# tiny-avionics.net
KiCad netlist of a schematic drawn in EAGLE
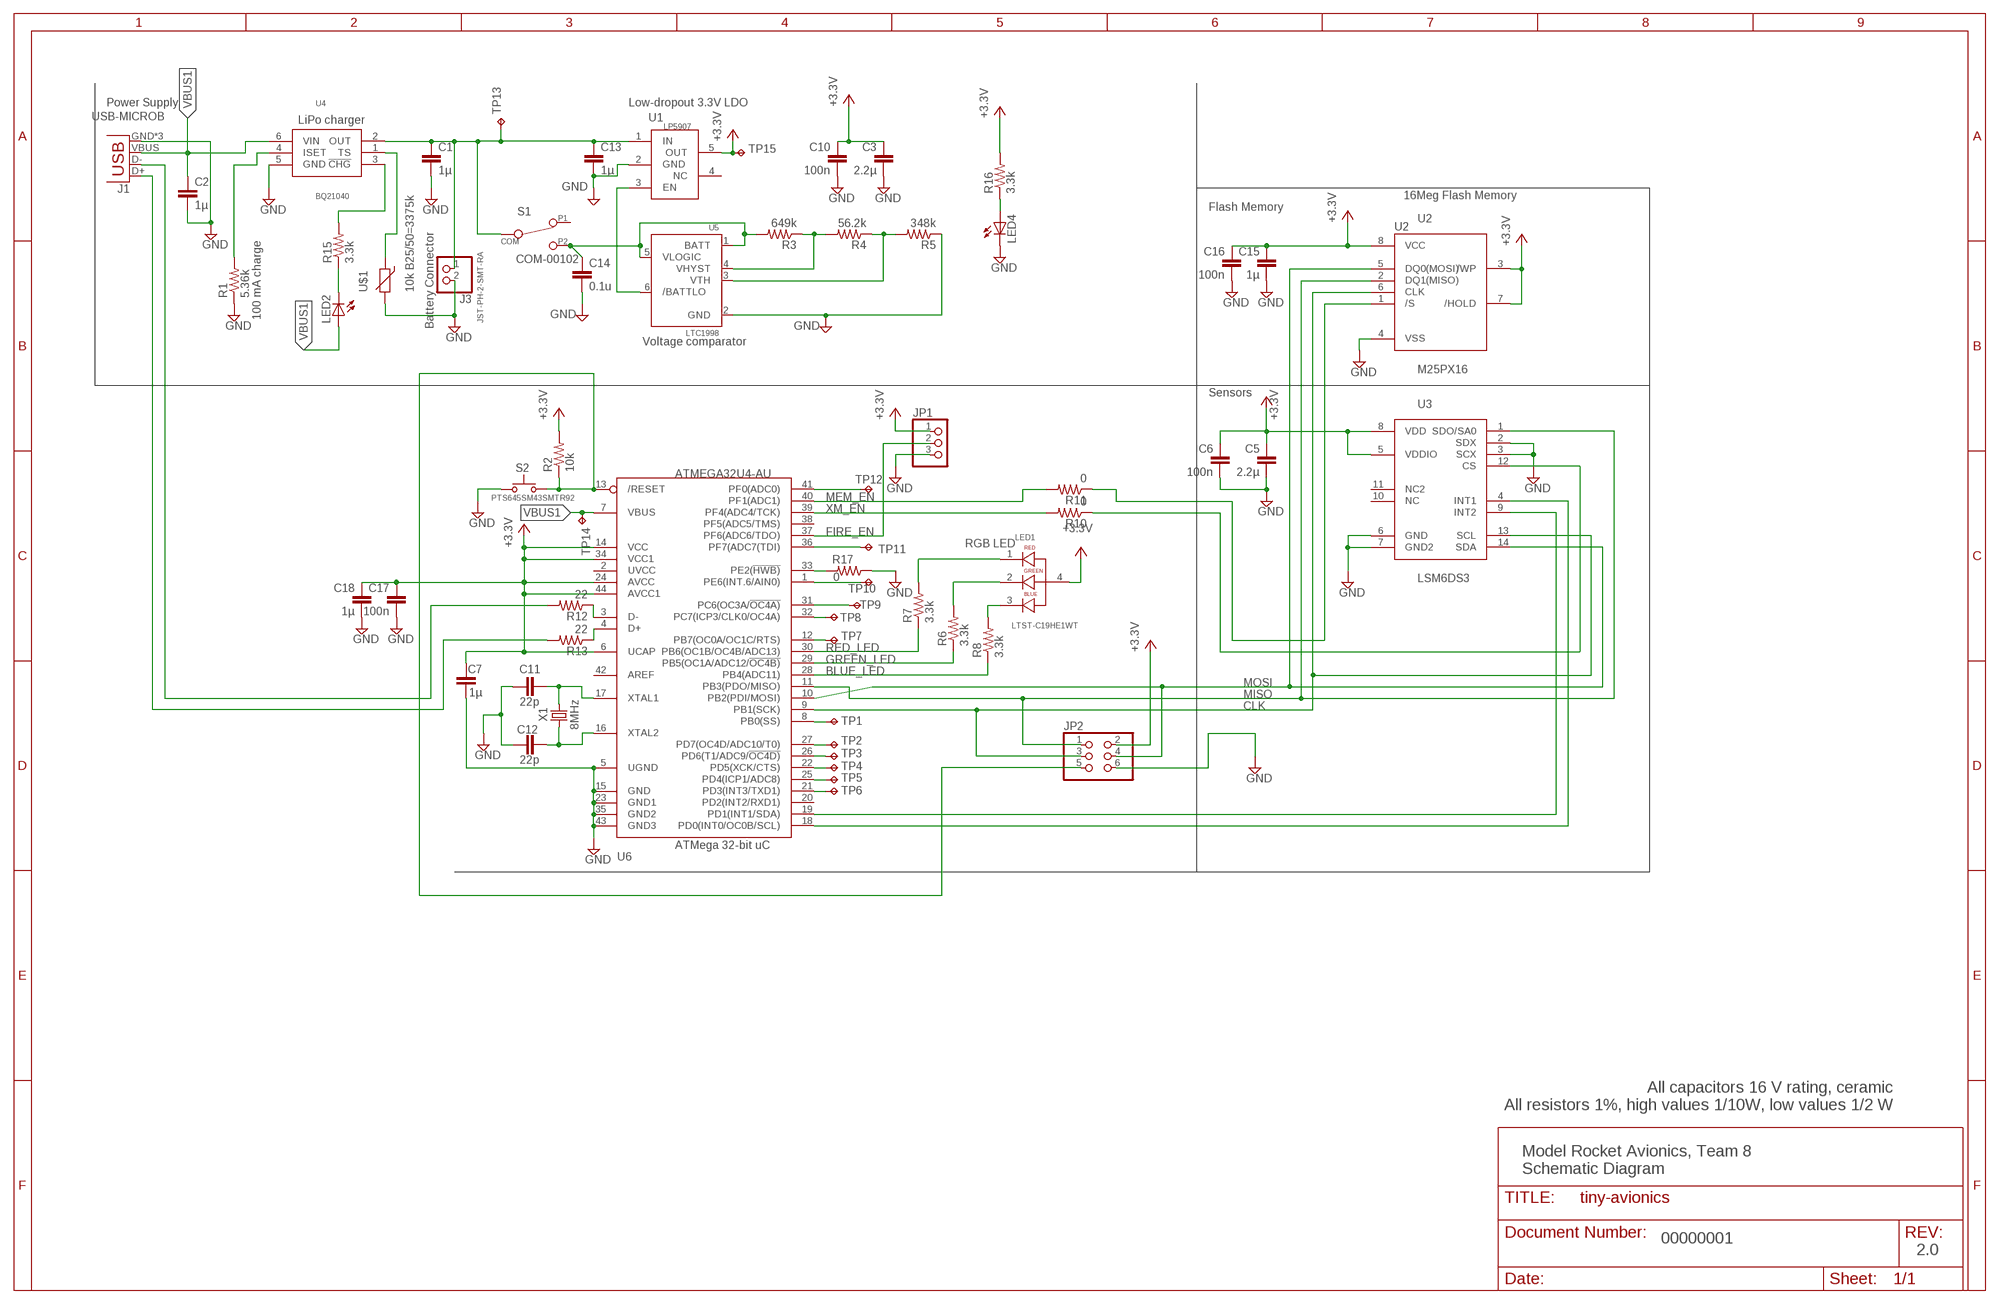
[diagram p0: schematic, sheet 1]

(export (version "E")
  (design (tool "Eeschema 10.0.6"))
  (components
    (comp (ref "C1")
      (value "1µ")
      (footprint "eagle-import:C0603")
      (libsource (lib "eagle-import") (part "C-EUC0603"))
    )
    (comp (ref "C2")
      (value "1µ")
      (footprint "eagle-import:C0603")
      (libsource (lib "eagle-import") (part "C-EUC0603"))
    )
    (comp (ref "C3")
      (value "2.2µ")
      (footprint "eagle-import:C0603")
      (libsource (lib "eagle-import") (part "C-EUC0603"))
    )
    (comp (ref "C5")
      (value "2.2µ")
      (footprint "eagle-import:C0603")
      (libsource (lib "eagle-import") (part "C-EUC0603"))
    )
    (comp (ref "C6")
      (value "100n")
      (footprint "eagle-import:C0603")
      (libsource (lib "eagle-import") (part "C-EUC0603"))
    )
    (comp (ref "C7")
      (value "1µ")
      (footprint "eagle-import:C0603")
      (libsource (lib "eagle-import") (part "C-EUC0603"))
    )
    (comp (ref "C10")
      (value "100n")
      (footprint "eagle-import:C0603")
      (libsource (lib "eagle-import") (part "C-EUC0603"))
    )
    (comp (ref "C11")
      (value "22p")
      (footprint "eagle-import:C0603")
      (libsource (lib "eagle-import") (part "C-EUC0603"))
    )
    (comp (ref "C12")
      (value "22p")
      (footprint "eagle-import:C0603")
      (libsource (lib "eagle-import") (part "C-EUC0603"))
    )
    (comp (ref "C13")
      (value "1µ")
      (footprint "eagle-import:C0603")
      (libsource (lib "eagle-import") (part "C-EUC0603"))
    )
    (comp (ref "C14")
      (value "0.1u")
      (footprint "eagle-import:C0603")
      (libsource (lib "eagle-import") (part "C-EUC0603"))
    )
    (comp (ref "C15")
      (value "1µ")
      (footprint "eagle-import:C0603")
      (libsource (lib "eagle-import") (part "C-EUC0603"))
    )
    (comp (ref "C16")
      (value "100n")
      (footprint "eagle-import:C0603")
      (libsource (lib "eagle-import") (part "C-EUC0603"))
    )
    (comp (ref "C17")
      (value "100n")
      (footprint "eagle-import:C0603")
      (libsource (lib "eagle-import") (part "C-EUC0603"))
    )
    (comp (ref "C18")
      (value "1µ")
      (footprint "eagle-import:C0603")
      (libsource (lib "eagle-import") (part "C-EUC0603"))
    )
    (comp (ref "J1")
      (value "USB-MICROB")
      (footprint "eagle-import:USB-MICROB")
      (libsource (lib "eagle-import") (part "USB-MICROB"))
    )
    (comp (ref "J3")
      (value "JST-PH-2-SMT-RA")
      (footprint "eagle-import:JST-PH-2-SMT-RA")
      (libsource (lib "eagle-import") (part "JST_2PIN-SMT-RA"))
    )
    (comp (ref "JP1")
      (value "PINHD-1X3")
      (footprint "eagle-import:1X03")
      (libsource (lib "eagle-import") (part "PINHD-1X3"))
    )
    (comp (ref "JP2")
      (value "PINHD-2X3")
      (footprint "eagle-import:2X03")
      (libsource (lib "eagle-import") (part "PINHD-2X3"))
    )
    (comp (ref "LED1")
      (value "LTST-C19HE1WT")
      (footprint "eagle-import:LEDSC85P160X160X35-4N")
      (fields (field (name "MF") "Lite-On") (field (name "PRICE") "0.59 USD"))
      (libsource (lib "eagle-import") (part "LTST-C19HE1WT"))
    )
    (comp (ref "LED2")
      (value "LEDCHIP-LED0603")
      (footprint "eagle-import:CHIP-LED0603")
      (libsource (lib "eagle-import") (part "LEDCHIP-LED0603"))
    )
    (comp (ref "LED4")
      (value "LEDCHIP-LED0603")
      (footprint "eagle-import:CHIP-LED0603")
      (libsource (lib "eagle-import") (part "LEDCHIP-LED0603"))
    )
    (comp (ref "R1")
      (value "5.36k")
      (footprint "eagle-import:R0603")
      (libsource (lib "eagle-import") (part "R-US_R0603"))
    )
    (comp (ref "R2")
      (value "10k")
      (footprint "eagle-import:R0603")
      (libsource (lib "eagle-import") (part "R-US_R0603"))
    )
    (comp (ref "R3")
      (value "649k")
      (footprint "eagle-import:R0603")
      (libsource (lib "eagle-import") (part "R-US_R0603"))
    )
    (comp (ref "R4")
      (value "56.2k")
      (footprint "eagle-import:R0603")
      (libsource (lib "eagle-import") (part "R-US_R0603"))
    )
    (comp (ref "R5")
      (value "348k")
      (footprint "eagle-import:R0603")
      (libsource (lib "eagle-import") (part "R-US_R0603"))
    )
    (comp (ref "R6")
      (value "3.3k")
      (footprint "eagle-import:R0603")
      (libsource (lib "eagle-import") (part "R-US_R0603"))
    )
    (comp (ref "R7")
      (value "3.3k")
      (footprint "eagle-import:R0603")
      (libsource (lib "eagle-import") (part "R-US_R0603"))
    )
    (comp (ref "R8")
      (value "3.3k")
      (footprint "eagle-import:R0603")
      (libsource (lib "eagle-import") (part "R-US_R0603"))
    )
    (comp (ref "R10")
      (value "0")
      (footprint "eagle-import:R0603")
      (libsource (lib "eagle-import") (part "R-US_R0603"))
    )
    (comp (ref "R11")
      (value "0")
      (footprint "eagle-import:R0603")
      (libsource (lib "eagle-import") (part "R-US_R0603"))
    )
    (comp (ref "R12")
      (value "22")
      (footprint "eagle-import:R0603")
      (libsource (lib "eagle-import") (part "R-US_R0603"))
    )
    (comp (ref "R13")
      (value "22")
      (footprint "eagle-import:R0603")
      (libsource (lib "eagle-import") (part "R-US_R0603"))
    )
    (comp (ref "R15")
      (value "3.3k")
      (footprint "eagle-import:R0603")
      (libsource (lib "eagle-import") (part "R-US_R0603"))
    )
    (comp (ref "R16")
      (value "3.3k")
      (footprint "eagle-import:R0603")
      (libsource (lib "eagle-import") (part "R-US_R0603"))
    )
    (comp (ref "R17")
      (value "0")
      (footprint "eagle-import:R0603")
      (libsource (lib "eagle-import") (part "R-US_R0603"))
    )
    (comp (ref "S1")
      (value "COM-00102")
      (footprint "eagle-import:ESWITCH")
      (libsource (lib "eagle-import") (part "COM-00102"))
    )
    (comp (ref "S2")
      (value "PTS645SM43SMTR92")
      (footprint "eagle-import:PTS645-SMD")
      (fields (field (name "MPN") "PTS645SM43SMTR92 LFS"))
      (libsource (lib "eagle-import") (part "PTS645S???SMTR"))
    )
    (comp (ref "TP1")
      (value "TPTP08R")
      (footprint "eagle-import:TP08R")
      (libsource (lib "eagle-import") (part "TPTP08R"))
    )
    (comp (ref "TP2")
      (value "TPTP08R")
      (footprint "eagle-import:TP08R")
      (libsource (lib "eagle-import") (part "TPTP08R"))
    )
    (comp (ref "TP3")
      (value "TPTP08R")
      (footprint "eagle-import:TP08R")
      (libsource (lib "eagle-import") (part "TPTP08R"))
    )
    (comp (ref "TP4")
      (value "TPTP08R")
      (footprint "eagle-import:TP08R")
      (libsource (lib "eagle-import") (part "TPTP08R"))
    )
    (comp (ref "TP5")
      (value "TPTP08R")
      (footprint "eagle-import:TP08R")
      (libsource (lib "eagle-import") (part "TPTP08R"))
    )
    (comp (ref "TP6")
      (value "TPTP08R")
      (footprint "eagle-import:TP08R")
      (libsource (lib "eagle-import") (part "TPTP08R"))
    )
    (comp (ref "TP7")
      (value "TPTP08R")
      (footprint "eagle-import:TP08R")
      (libsource (lib "eagle-import") (part "TPTP08R"))
    )
    (comp (ref "TP8")
      (value "TPTP08R")
      (footprint "eagle-import:TP08R")
      (libsource (lib "eagle-import") (part "TPTP08R"))
    )
    (comp (ref "TP9")
      (value "TPTP08R")
      (footprint "eagle-import:TP08R")
      (libsource (lib "eagle-import") (part "TPTP08R"))
    )
    (comp (ref "TP10")
      (value "TPTP08R")
      (footprint "eagle-import:TP08R")
      (libsource (lib "eagle-import") (part "TPTP08R"))
    )
    (comp (ref "TP11")
      (value "TPTP08R")
      (footprint "eagle-import:TP08R")
      (libsource (lib "eagle-import") (part "TPTP08R"))
    )
    (comp (ref "TP12")
      (value "TPTP08R")
      (footprint "eagle-import:TP08R")
      (libsource (lib "eagle-import") (part "TPTP08R"))
    )
    (comp (ref "TP13")
      (value "TPTP08R")
      (footprint "eagle-import:TP08R")
      (libsource (lib "eagle-import") (part "TPTP08R"))
    )
    (comp (ref "TP14")
      (value "TPTP08R")
      (footprint "eagle-import:TP08R")
      (libsource (lib "eagle-import") (part "TPTP08R"))
    )
    (comp (ref "TP15")
      (value "TPTP08R")
      (footprint "eagle-import:TP08R")
      (libsource (lib "eagle-import") (part "TPTP08R"))
    )
    (comp (ref "U$1")
      (value "10k B25/50=3375k")
      (footprint "eagle-import:R0603")
      (libsource (lib "eagle-import") (part "THERMISTOR-SMD0603"))
    )
    (comp (ref "U1")
      (value "LP5907")
      (footprint "eagle-import:SOT23-5L")
      (libsource (lib "eagle-import") (part "LP5907"))
    )
    (comp (ref "U2")
      (value "M25PX16")
      (footprint "eagle-import:SO8")
      (libsource (lib "eagle-import") (part "M25PX16"))
    )
    (comp (ref "U3")
      (value "LSM6DS3")
      (footprint "eagle-import:LGA-14L")
      (libsource (lib "eagle-import") (part "LSM6DS3"))
    )
    (comp (ref "U4")
      (value "BQ21040")
      (footprint "eagle-import:SOT23-6L")
      (libsource (lib "eagle-import") (part "BQ21040"))
    )
    (comp (ref "U5")
      (value "LTC1998")
      (footprint "eagle-import:TSOT23-6")
      (libsource (lib "eagle-import") (part "LTC1998"))
    )
    (comp (ref "U6")
      (value "ATMEGA32U4-AU")
      (footprint "eagle-import:TQFP44")
      (libsource (lib "eagle-import") (part "ATMEGA32U4-AU"))
    )
    (comp (ref "X1")
      (value "8MHz")
      (footprint "eagle-import:ATS-SM")
      (fields (field (name "MPN") "ATS080B"))
      (libsource (lib "eagle-import") (part "CRYSTAL-NOGND-SMD"))
    )
  )
  (nets
    (net (code "1") (name "+3.3V") (class "Default")
      (node (ref "C10") (pin "1") (pinfunction "1_1") (pintype "passive"))
      (node (ref "C15") (pin "1") (pinfunction "1_1") (pintype "passive"))
      (node (ref "C16") (pin "1") (pinfunction "1_1") (pintype "passive"))
      (node (ref "C17") (pin "1") (pinfunction "1_1") (pintype "passive"))
      (node (ref "C18") (pin "1") (pinfunction "1_1") (pintype "passive"))
      (node (ref "C3") (pin "1") (pinfunction "1_1") (pintype "passive"))
      (node (ref "C5") (pin "1") (pinfunction "1_1") (pintype "passive"))
      (node (ref "C6") (pin "1") (pinfunction "1_1") (pintype "passive"))
      (node (ref "C7") (pin "1") (pinfunction "1_1") (pintype "passive"))
      (node (ref "JP1") (pin "1") (pinfunction "1_1") (pintype "passive"))
      (node (ref "JP2") (pin "2") (pinfunction "2_2") (pintype "passive"))
      (node (ref "LED1") (pin "4") (pinfunction "4_4") (pintype "passive"))
      (node (ref "R16") (pin "2") (pinfunction "2_2") (pintype "passive"))
      (node (ref "R2") (pin "2") (pinfunction "2_2") (pintype "passive"))
      (node (ref "TP15") (pin "TP") (pinfunction "TP_TP") (pintype "input"))
      (node (ref "U1") (pin "5") (pinfunction "OUT_5") (pintype "bidirectional"))
      (node (ref "U2") (pin "3") (pinfunction "/WP_3") (pintype "bidirectional"))
      (node (ref "U2") (pin "7") (pinfunction "/HOLD_7") (pintype "bidirectional"))
      (node (ref "U2") (pin "8") (pinfunction "VCC_8") (pintype "bidirectional"))
      (node (ref "U3") (pin "5") (pinfunction "VDDIO_5") (pintype "bidirectional"))
      (node (ref "U3") (pin "8") (pinfunction "VDD_8") (pintype "bidirectional"))
      (node (ref "U6") (pin "14") (pinfunction "VCC_14") (pintype "bidirectional"))
      (node (ref "U6") (pin "24") (pinfunction "AVCC_24") (pintype "bidirectional"))
      (node (ref "U6") (pin "34") (pinfunction "VCC1_34") (pintype "bidirectional"))
      (node (ref "U6") (pin "44") (pinfunction "AVCC1_44") (pintype "bidirectional"))
      (node (ref "U6") (pin "6") (pinfunction "UCAP_6") (pintype "bidirectional"))
    )
    (net (code "2") (name "/BLUE_LED") (class "Default")
      (node (ref "R8") (pin "1") (pinfunction "1_1") (pintype "passive"))
      (node (ref "U6") (pin "28") (pinfunction "PB4(ADC11)_28") (pintype "bidirectional"))
    )
    (net (code "3") (name "/CLK") (class "Default")
      (node (ref "JP2") (pin "3") (pinfunction "3_3") (pintype "passive"))
      (node (ref "U2") (pin "6") (pinfunction "CLK_6") (pintype "bidirectional"))
      (node (ref "U3") (pin "13") (pinfunction "SCL_13") (pintype "bidirectional"))
      (node (ref "U6") (pin "9") (pinfunction "PB1(SCK)_9") (pintype "bidirectional"))
    )
    (net (code "4") (name "/FIRE_EN") (class "Default")
      (node (ref "JP1") (pin "2") (pinfunction "2_2") (pintype "passive"))
      (node (ref "U6") (pin "37") (pinfunction "PF6(ADC6/TDO)_37") (pintype "bidirectional"))
    )
    (net (code "5") (name "/GREEN_LED") (class "Default")
      (node (ref "R6") (pin "1") (pinfunction "1_1") (pintype "passive"))
      (node (ref "U6") (pin "29") (pinfunction "PB5(OC1A/ADC12/~{OC4B})_29") (pintype "bidirectional"))
    )
    (net (code "6") (name "/MEM_EN") (class "Default")
      (node (ref "R11") (pin "1") (pinfunction "1_1") (pintype "passive"))
      (node (ref "U2") (pin "1") (pinfunction "/S_1") (pintype "bidirectional"))
    )
    (net (code "7") (name "/MISO") (class "Default")
      (node (ref "JP2") (pin "1") (pinfunction "1_1") (pintype "passive"))
      (node (ref "U2") (pin "2") (pinfunction "DQ1(MISO)_2") (pintype "bidirectional"))
      (node (ref "U3") (pin "1") (pinfunction "SDO/SA0_1") (pintype "bidirectional"))
      (node (ref "U6") (pin "11") (pinfunction "PB3(PDO/MISO)_11") (pintype "bidirectional"))
    )
    (net (code "8") (name "/MOSI") (class "Default")
      (node (ref "JP2") (pin "4") (pinfunction "4_4") (pintype "passive"))
      (node (ref "U2") (pin "5") (pinfunction "DQ0(MOSI)_5") (pintype "bidirectional"))
      (node (ref "U3") (pin "14") (pinfunction "SDA_14") (pintype "bidirectional"))
      (node (ref "U6") (pin "10") (pinfunction "PB2(PDI/MOSI)_10") (pintype "bidirectional"))
    )
    (net (code "9") (name "/RED_LED") (class "Default")
      (node (ref "R7") (pin "1") (pinfunction "1_1") (pintype "passive"))
      (node (ref "U6") (pin "30") (pinfunction "PB6(OC1B/OC4B/ADC13)_30") (pintype "bidirectional"))
    )
    (net (code "10") (name "/XM_EN") (class "Default")
      (node (ref "R10") (pin "1") (pinfunction "1_1") (pintype "passive"))
      (node (ref "U3") (pin "12") (pinfunction "CS_12") (pintype "bidirectional"))
    )
    (net (code "11") (name "GND") (class "Default")
      (node (ref "C1") (pin "2") (pinfunction "2_2") (pintype "passive"))
      (node (ref "C10") (pin "2") (pinfunction "2_2") (pintype "passive"))
      (node (ref "C11") (pin "2") (pinfunction "2_2") (pintype "passive"))
      (node (ref "C12") (pin "2") (pinfunction "2_2") (pintype "passive"))
      (node (ref "C13") (pin "2") (pinfunction "2_2") (pintype "passive"))
      (node (ref "C14") (pin "2") (pinfunction "2_2") (pintype "passive"))
      (node (ref "C15") (pin "2") (pinfunction "2_2") (pintype "passive"))
      (node (ref "C16") (pin "2") (pinfunction "2_2") (pintype "passive"))
      (node (ref "C17") (pin "2") (pinfunction "2_2") (pintype "passive"))
      (node (ref "C18") (pin "2") (pinfunction "2_2") (pintype "passive"))
      (node (ref "C2") (pin "2") (pinfunction "2_2") (pintype "passive"))
      (node (ref "C3") (pin "2") (pinfunction "2_2") (pintype "passive"))
      (node (ref "C5") (pin "2") (pinfunction "2_2") (pintype "passive"))
      (node (ref "C6") (pin "2") (pinfunction "2_2") (pintype "passive"))
      (node (ref "C7") (pin "2") (pinfunction "2_2") (pintype "passive"))
      (node (ref "J1") (pin "GND") (pinfunction "GND_GND") (pintype "bidirectional"))
      (node (ref "J1") (pin "MT1") (pinfunction "GND_MT1") (pintype "bidirectional"))
      (node (ref "J1") (pin "MT2") (pinfunction "GND_MT2") (pintype "bidirectional"))
      (node (ref "J3") (pin "2") (pinfunction "1_2") (pintype "passive"))
      (node (ref "JP1") (pin "3") (pinfunction "3_3") (pintype "passive"))
      (node (ref "JP2") (pin "6") (pinfunction "6_6") (pintype "passive"))
      (node (ref "LED4") (pin "C") (pinfunction "C_C") (pintype "passive"))
      (node (ref "R1") (pin "1") (pinfunction "1_1") (pintype "passive"))
      (node (ref "R17") (pin "1") (pinfunction "1_1") (pintype "passive"))
      (node (ref "R5") (pin "1") (pinfunction "1_1") (pintype "passive"))
      (node (ref "S2") (pin "1") (pinfunction "P_1") (pintype "passive"))
      (node (ref "S2") (pin "2") (pinfunction "P_2") (pintype "passive"))
      (node (ref "U$1") (pin "2") (pinfunction "2_2") (pintype "passive"))
      (node (ref "U1") (pin "2") (pinfunction "GND_2") (pintype "bidirectional"))
      (node (ref "U2") (pin "4") (pinfunction "VSS_4") (pintype "bidirectional"))
      (node (ref "U3") (pin "2") (pinfunction "SDX_2") (pintype "bidirectional"))
      (node (ref "U3") (pin "3") (pinfunction "SCX_3") (pintype "bidirectional"))
      (node (ref "U3") (pin "6") (pinfunction "GND_6") (pintype "bidirectional"))
      (node (ref "U3") (pin "7") (pinfunction "GND2_7") (pintype "bidirectional"))
      (node (ref "U4") (pin "5") (pinfunction "GND_5") (pintype "bidirectional"))
      (node (ref "U5") (pin "2") (pinfunction "GND_2") (pintype "bidirectional"))
      (node (ref "U6") (pin "15") (pinfunction "GND_15") (pintype "bidirectional"))
      (node (ref "U6") (pin "23") (pinfunction "GND1_23") (pintype "bidirectional"))
      (node (ref "U6") (pin "35") (pinfunction "GND2_35") (pintype "bidirectional"))
      (node (ref "U6") (pin "43") (pinfunction "GND3_43") (pintype "bidirectional"))
      (node (ref "U6") (pin "5") (pinfunction "UGND_5") (pintype "bidirectional"))
    )
    (net (code "12") (name "Net-(J1-PadD+)") (class "Default")
      (node (ref "J1") (pin "D+") (pinfunction "D+_D+") (pintype "bidirectional"))
      (node (ref "R13") (pin "2") (pinfunction "2_2") (pintype "passive"))
    )
    (net (code "13") (name "Net-(J1-PadD-)") (class "Default")
      (node (ref "J1") (pin "D-") (pinfunction "D-_D-") (pintype "bidirectional"))
      (node (ref "R12") (pin "2") (pinfunction "2_2") (pintype "passive"))
    )
    (net (code "14") (name "Net-(J3-2)") (class "Default")
      (node (ref "C1") (pin "1") (pinfunction "1_1") (pintype "passive"))
      (node (ref "C13") (pin "1") (pinfunction "1_1") (pintype "passive"))
      (node (ref "J3") (pin "1") (pinfunction "2_1") (pintype "passive"))
      (node (ref "S1") (pin "2") (pinfunction "COM_2") (pintype "bidirectional"))
      (node (ref "TP13") (pin "TP") (pinfunction "TP_TP") (pintype "input"))
      (node (ref "U1") (pin "1") (pinfunction "IN_1") (pintype "bidirectional"))
      (node (ref "U4") (pin "2") (pinfunction "OUT_2") (pintype "bidirectional"))
    )
    (net (code "15") (name "Net-(LED1-Pad1)") (class "Default")
      (node (ref "LED1") (pin "1") (pinfunction "1_1") (pintype "passive"))
      (node (ref "R7") (pin "2") (pinfunction "2_2") (pintype "passive"))
    )
    (net (code "16") (name "Net-(LED1-Pad2)") (class "Default")
      (node (ref "LED1") (pin "2") (pinfunction "2_2") (pintype "passive"))
      (node (ref "R6") (pin "2") (pinfunction "2_2") (pintype "passive"))
    )
    (net (code "17") (name "Net-(LED1-Pad3)") (class "Default")
      (node (ref "LED1") (pin "3") (pinfunction "3_3") (pintype "passive"))
      (node (ref "R8") (pin "2") (pinfunction "2_2") (pintype "passive"))
    )
    (net (code "18") (name "Net-(LED2-PadC)") (class "Default")
      (node (ref "LED2") (pin "C") (pinfunction "C_C") (pintype "passive"))
      (node (ref "R15") (pin "1") (pinfunction "1_1") (pintype "passive"))
    )
    (net (code "19") (name "Net-(LED4-PadA)") (class "Default")
      (node (ref "LED4") (pin "A") (pinfunction "A_A") (pintype "passive"))
      (node (ref "R16") (pin "1") (pinfunction "1_1") (pintype "passive"))
    )
    (net (code "20") (name "Net-(S1-P2)") (class "Default")
      (node (ref "C14") (pin "1") (pinfunction "1_1") (pintype "passive"))
      (node (ref "R3") (pin "2") (pinfunction "2_2") (pintype "passive"))
      (node (ref "S1") (pin "3") (pinfunction "P2_3") (pintype "bidirectional"))
      (node (ref "U5") (pin "1") (pinfunction "BATT_1") (pintype "bidirectional"))
      (node (ref "U5") (pin "5") (pinfunction "VLOGIC_5") (pintype "bidirectional"))
    )
    (net (code "21") (name "Net-(U1-EN)") (class "Default")
      (node (ref "U1") (pin "3") (pinfunction "EN_3") (pintype "bidirectional"))
      (node (ref "U5") (pin "6") (pinfunction "/BATTLO_6") (pintype "bidirectional"))
    )
    (net (code "22") (name "Net-(U3-INT1)") (class "Default")
      (node (ref "U3") (pin "4") (pinfunction "INT1_4") (pintype "bidirectional"))
      (node (ref "U6") (pin "18") (pinfunction "PD0(INT0/OC0B/SCL)_18") (pintype "bidirectional"))
    )
    (net (code "23") (name "Net-(U3-INT2)") (class "Default")
      (node (ref "U3") (pin "9") (pinfunction "INT2_9") (pintype "bidirectional"))
      (node (ref "U6") (pin "19") (pinfunction "PD1(INT1/SDA)_19") (pintype "bidirectional"))
    )
    (net (code "24") (name "Net-(U4-ISET)") (class "Default")
      (node (ref "R1") (pin "2") (pinfunction "2_2") (pintype "passive"))
      (node (ref "U4") (pin "4") (pinfunction "ISET_4") (pintype "bidirectional"))
    )
    (net (code "25") (name "Net-(U4-TS)") (class "Default")
      (node (ref "U$1") (pin "1") (pinfunction "1_1") (pintype "passive"))
      (node (ref "U4") (pin "1") (pinfunction "TS_1") (pintype "bidirectional"))
    )
    (net (code "26") (name "Net-(U4-~{CHG})") (class "Default")
      (node (ref "R15") (pin "2") (pinfunction "2_2") (pintype "passive"))
      (node (ref "U4") (pin "3") (pinfunction "~{CHG}_3") (pintype "bidirectional"))
    )
    (net (code "27") (name "Net-(U5-VHYST)") (class "Default")
      (node (ref "R3") (pin "1") (pinfunction "1_1") (pintype "passive"))
      (node (ref "R4") (pin "2") (pinfunction "2_2") (pintype "passive"))
      (node (ref "U5") (pin "4") (pinfunction "VHYST_4") (pintype "bidirectional"))
    )
    (net (code "28") (name "Net-(U5-VTH)") (class "Default")
      (node (ref "R4") (pin "1") (pinfunction "1_1") (pintype "passive"))
      (node (ref "R5") (pin "2") (pinfunction "2_2") (pintype "passive"))
      (node (ref "U5") (pin "3") (pinfunction "VTH_3") (pintype "bidirectional"))
    )
    (net (code "29") (name "Net-(U6-D+)") (class "Default")
      (node (ref "R13") (pin "1") (pinfunction "1_1") (pintype "passive"))
      (node (ref "U6") (pin "4") (pinfunction "D+_4") (pintype "bidirectional"))
    )
    (net (code "30") (name "Net-(U6-D-)") (class "Default")
      (node (ref "R12") (pin "1") (pinfunction "1_1") (pintype "passive"))
      (node (ref "U6") (pin "3") (pinfunction "D-_3") (pintype "bidirectional"))
    )
    (net (code "31") (name "Net-(U6-PB0(SS))") (class "Default")
      (node (ref "TP1") (pin "TP") (pinfunction "TP_TP") (pintype "input"))
      (node (ref "U6") (pin "8") (pinfunction "PB0(SS)_8") (pintype "bidirectional"))
    )
    (net (code "32") (name "Net-(U6-PB7(OC0A{slash}OC1C{slash}RTS))") (class "Default")
      (node (ref "TP7") (pin "TP") (pinfunction "TP_TP") (pintype "input"))
      (node (ref "U6") (pin "12") (pinfunction "PB7(OC0A/OC1C/RTS)_12") (pintype "bidirectional"))
    )
    (net (code "33") (name "Net-(U6-PC6(OC3A{slash}~{OC4A}))") (class "Default")
      (node (ref "TP9") (pin "TP") (pinfunction "TP_TP") (pintype "input"))
      (node (ref "U6") (pin "31") (pinfunction "PC6(OC3A/~{OC4A})_31") (pintype "bidirectional"))
    )
    (net (code "34") (name "Net-(U6-PC7(ICP3{slash}CLK0{slash}OC4A))") (class "Default")
      (node (ref "TP8") (pin "TP") (pinfunction "TP_TP") (pintype "input"))
      (node (ref "U6") (pin "32") (pinfunction "PC7(ICP3/CLK0/OC4A)_32") (pintype "bidirectional"))
    )
    (net (code "35") (name "Net-(U6-PD3(INT3{slash}TXD1))") (class "Default")
      (node (ref "TP6") (pin "TP") (pinfunction "TP_TP") (pintype "input"))
      (node (ref "U6") (pin "21") (pinfunction "PD3(INT3/TXD1)_21") (pintype "bidirectional"))
    )
    (net (code "36") (name "Net-(U6-PD4(ICP1{slash}ADC8))") (class "Default")
      (node (ref "TP5") (pin "TP") (pinfunction "TP_TP") (pintype "input"))
      (node (ref "U6") (pin "25") (pinfunction "PD4(ICP1/ADC8)_25") (pintype "bidirectional"))
    )
    (net (code "37") (name "Net-(U6-PD5(XCK{slash}CTS))") (class "Default")
      (node (ref "TP4") (pin "TP") (pinfunction "TP_TP") (pintype "input"))
      (node (ref "U6") (pin "22") (pinfunction "PD5(XCK/CTS)_22") (pintype "bidirectional"))
    )
    (net (code "38") (name "Net-(U6-PD6(T1{slash}ADC9{slash}~{OC4D}))") (class "Default")
      (node (ref "TP3") (pin "TP") (pinfunction "TP_TP") (pintype "input"))
      (node (ref "U6") (pin "26") (pinfunction "PD6(T1/ADC9/~{OC4D})_26") (pintype "bidirectional"))
    )
    (net (code "39") (name "Net-(U6-PD7(OC4D{slash}ADC10{slash}T0))") (class "Default")
      (node (ref "TP2") (pin "TP") (pinfunction "TP_TP") (pintype "input"))
      (node (ref "U6") (pin "27") (pinfunction "PD7(OC4D/ADC10/T0)_27") (pintype "bidirectional"))
    )
    (net (code "40") (name "Net-(U6-PE2(~{HWB}))") (class "Default")
      (node (ref "R17") (pin "2") (pinfunction "2_2") (pintype "passive"))
      (node (ref "U6") (pin "33") (pinfunction "PE2(~{HWB})_33") (pintype "bidirectional"))
    )
    (net (code "41") (name "Net-(U6-PE6(INT.6{slash}AIN0))") (class "Default")
      (node (ref "TP10") (pin "TP") (pinfunction "TP_TP") (pintype "input"))
      (node (ref "U6") (pin "1") (pinfunction "PE6(INT.6/AIN0)_1") (pintype "bidirectional"))
    )
    (net (code "42") (name "Net-(U6-PF0(ADC0))") (class "Default")
      (node (ref "TP12") (pin "TP") (pinfunction "TP_TP") (pintype "input"))
      (node (ref "U6") (pin "41") (pinfunction "PF0(ADC0)_41") (pintype "bidirectional"))
    )
    (net (code "43") (name "Net-(U6-PF1(ADC1))") (class "Default")
      (node (ref "R11") (pin "2") (pinfunction "2_2") (pintype "passive"))
      (node (ref "U6") (pin "40") (pinfunction "PF1(ADC1)_40") (pintype "bidirectional"))
    )
    (net (code "44") (name "Net-(U6-PF4(ADC4{slash}TCK))") (class "Default")
      (node (ref "R10") (pin "2") (pinfunction "2_2") (pintype "passive"))
      (node (ref "U6") (pin "39") (pinfunction "PF4(ADC4/TCK)_39") (pintype "bidirectional"))
    )
    (net (code "45") (name "Net-(U6-PF7(ADC7(TDI))") (class "Default")
      (node (ref "TP11") (pin "TP") (pinfunction "TP_TP") (pintype "input"))
      (node (ref "U6") (pin "36") (pinfunction "PF7(ADC7(TDI)_36") (pintype "bidirectional"))
    )
    (net (code "46") (name "Net-(U6-XTAL1)") (class "Default")
      (node (ref "C11") (pin "1") (pinfunction "1_1") (pintype "passive"))
      (node (ref "U6") (pin "17") (pinfunction "XTAL1_17") (pintype "bidirectional"))
      (node (ref "X1") (pin "1") (pinfunction "1_1") (pintype "passive"))
    )
    (net (code "47") (name "Net-(U6-XTAL2)") (class "Default")
      (node (ref "C12") (pin "1") (pinfunction "1_1") (pintype "passive"))
      (node (ref "U6") (pin "16") (pinfunction "XTAL2_16") (pintype "bidirectional"))
      (node (ref "X1") (pin "2") (pinfunction "2_2") (pintype "passive"))
    )
    (net (code "48") (name "Net-(U6-{slash}RESET)") (class "Default")
      (node (ref "JP2") (pin "5") (pinfunction "5_5") (pintype "passive"))
      (node (ref "R2") (pin "1") (pinfunction "1_1") (pintype "passive"))
      (node (ref "S2") (pin "3") (pinfunction "S_3") (pintype "passive"))
      (node (ref "S2") (pin "4") (pinfunction "S_4") (pintype "passive"))
      (node (ref "U6") (pin "13") (pinfunction "/RESET_13") (pintype "bidirectional"))
    )
    (net (code "49") (name "VBUS1") (class "Default")
      (node (ref "C2") (pin "1") (pinfunction "1_1") (pintype "passive"))
      (node (ref "J1") (pin "VBUS") (pinfunction "VBUS_VBUS") (pintype "bidirectional"))
      (node (ref "LED2") (pin "A") (pinfunction "A_A") (pintype "passive"))
      (node (ref "TP14") (pin "TP") (pinfunction "TP_TP") (pintype "input"))
      (node (ref "U4") (pin "6") (pinfunction "VIN_6") (pintype "bidirectional"))
      (node (ref "U6") (pin "7") (pinfunction "VBUS_7") (pintype "bidirectional"))
    )
    (net (code "50") (name "unconnected-(S1-P1-Pad1)") (class "Default")
      (node (ref "S1") (pin "1") (pinfunction "P1_1") (pintype "bidirectional"))
    )
    (net (code "51") (name "unconnected-(U1-NC-Pad4)") (class "Default")
      (node (ref "U1") (pin "4") (pinfunction "NC_4") (pintype "bidirectional"))
    )
    (net (code "52") (name "unconnected-(U3-NC-Pad10)") (class "Default")
      (node (ref "U3") (pin "10") (pinfunction "NC_10") (pintype "bidirectional"))
    )
    (net (code "53") (name "unconnected-(U3-NC2-Pad11)") (class "Default")
      (node (ref "U3") (pin "11") (pinfunction "NC2_11") (pintype "bidirectional"))
    )
    (net (code "54") (name "unconnected-(U6-AREF-Pad42)") (class "Default")
      (node (ref "U6") (pin "42") (pinfunction "AREF_42") (pintype "bidirectional"))
    )
    (net (code "55") (name "unconnected-(U6-PD2(INT2{slash}RXD1)-Pad20)") (class "Default")
      (node (ref "U6") (pin "20") (pinfunction "PD2(INT2/RXD1)_20") (pintype "bidirectional"))
    )
    (net (code "56") (name "unconnected-(U6-PF5(ADC5{slash}TMS)-Pad38)") (class "Default")
      (node (ref "U6") (pin "38") (pinfunction "PF5(ADC5/TMS)_38") (pintype "bidirectional"))
    )
    (net (code "57") (name "unconnected-(U6-UVCC-Pad2)") (class "Default")
      (node (ref "U6") (pin "2") (pinfunction "UVCC_2") (pintype "bidirectional"))
    )
  )
)
